# OSSI-1_COMMS_3.net
KiCad netlist of a schematic drawn in Altium Designer
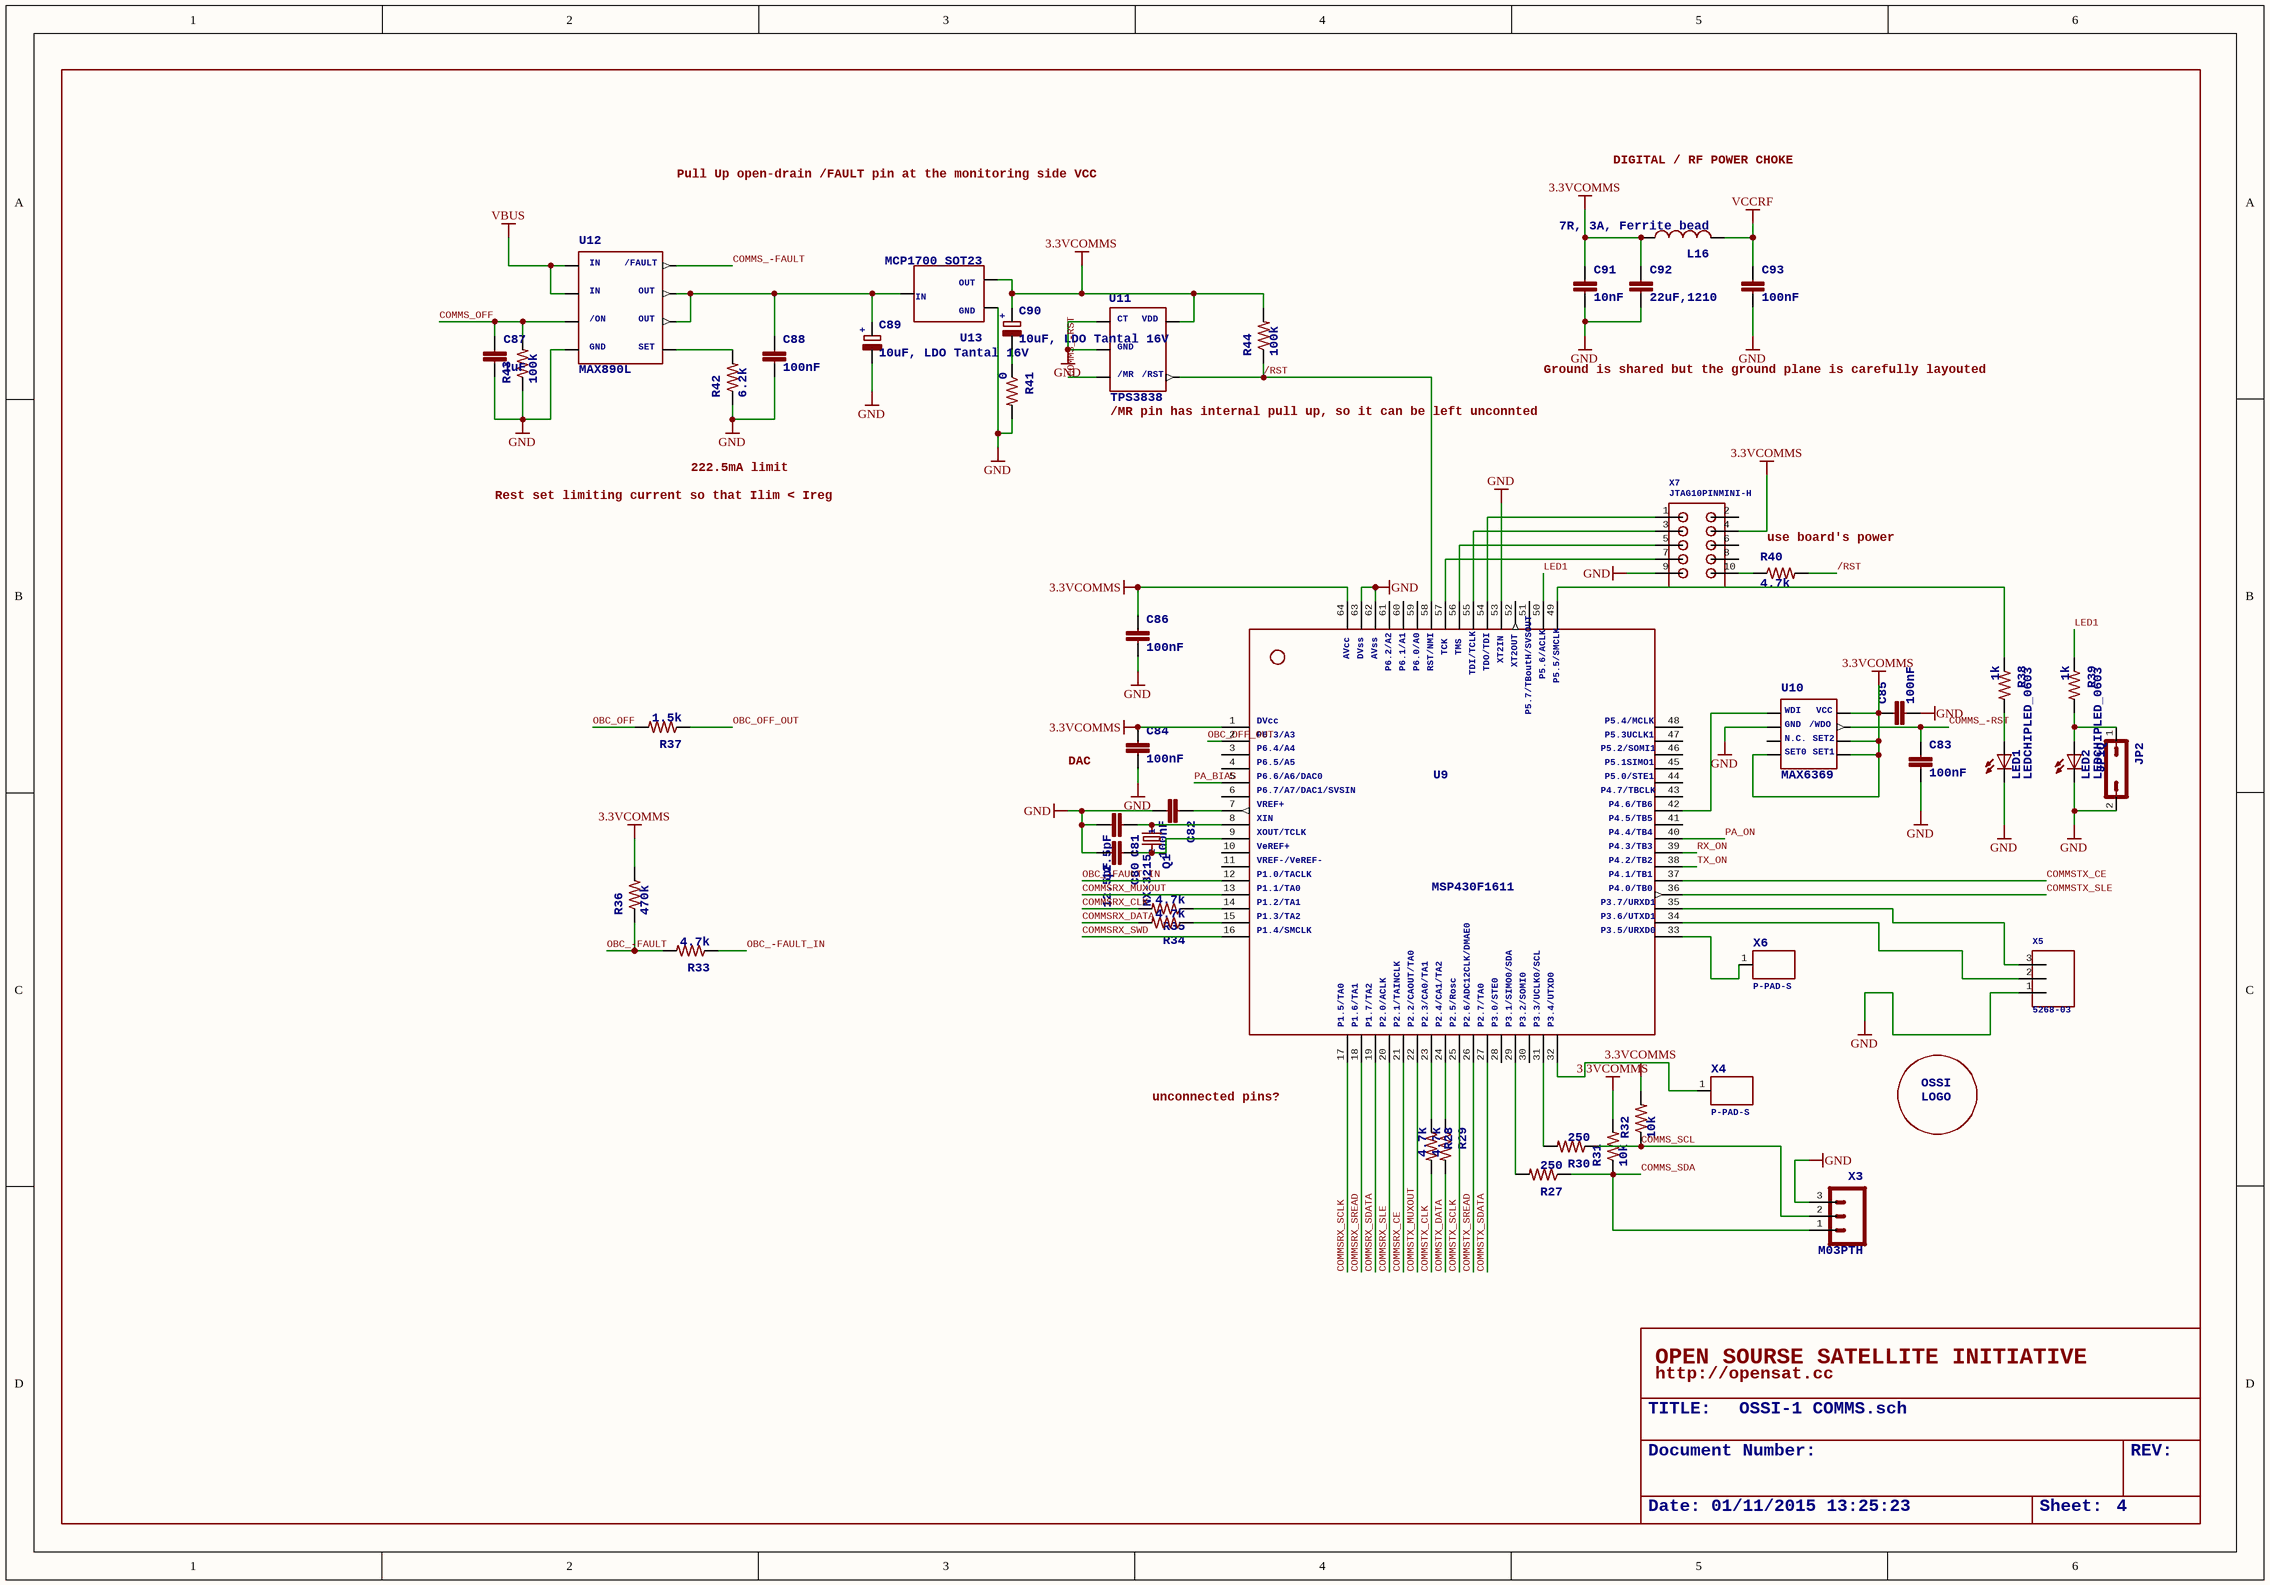
[diagram p0: OSSI-1 COMMS_3.SchDoc]

(export (version "E")
  (design (tool "Eeschema 10.0.6"))
  (components
    (comp (ref "C80")
      (value "12.5pF")
      (footprint "C0603(1608)")
      (fields (field (name ">NAME") "C80") (field (name ">VALUE") "12.5pF"))
      (libsource (lib "OSSI") (part "C0603(1608)"))
    )
    (comp (ref "C81")
      (value "12.5pF")
      (footprint "C0603(1608)")
      (fields (field (name ">NAME") "C81") (field (name ">VALUE") "12.5pF"))
      (libsource (lib "OSSI") (part "C0603(1608)"))
    )
    (comp (ref "C82")
      (value "100nF")
      (footprint "C0603(1608)")
      (fields (field (name ">NAME") "C82") (field (name ">VALUE") "100nF"))
      (libsource (lib "OSSI") (part "C0603(1608)"))
    )
    (comp (ref "C83")
      (value "100nF")
      (footprint "C0603(1608)")
      (fields (field (name ">NAME") "C83") (field (name ">VALUE") "100nF"))
      (libsource (lib "") (part "C0603(1608)_1"))
    )
    (comp (ref "C84")
      (value "100nF")
      (footprint "C0603(1608)")
      (fields (field (name ">NAME") "C84") (field (name ">VALUE") "100nF"))
      (libsource (lib "") (part "C0603(1608)_1"))
    )
    (comp (ref "C85")
      (value "100nF")
      (footprint "C0603(1608)")
      (fields (field (name ">NAME") "C85") (field (name ">VALUE") "100nF"))
      (libsource (lib "") (part "C0603(1608)_2"))
    )
    (comp (ref "C86")
      (value "100nF")
      (footprint "C0603(1608)")
      (fields (field (name ">NAME") "C86") (field (name ">VALUE") "100nF"))
      (libsource (lib "") (part "C0603(1608)_1"))
    )
    (comp (ref "C87")
      (value "1uF")
      (footprint "C0603(1608)")
      (fields (field (name ">NAME") "C87") (field (name ">VALUE") "1uF"))
      (libsource (lib "") (part "C0603(1608)_1"))
    )
    (comp (ref "C88")
      (value "100nF")
      (footprint "C0603(1608)")
      (fields (field (name ">NAME") "C88") (field (name ">VALUE") "100nF"))
      (libsource (lib "") (part "C0603(1608)_1"))
    )
    (comp (ref "C89")
      (value "10uF, LDO Tantal 16V")
      (footprint "C1206(3216)-A")
      (fields
        (field (name ">NAME") "C89")
        (field (name "+") "+")
        (field (name ">VALUE") "10uF, LDO Tantal 16V")
      )
      (libsource (lib "OSSI") (part "C-TANTAL-A"))
    )
    (comp (ref "C90")
      (value "10uF, LDO Tantal 16V")
      (footprint "C1206(3216)-A")
      (fields
        (field (name ">NAME") "C90")
        (field (name "+") "+")
        (field (name ">VALUE") "10uF, LDO Tantal 16V")
      )
      (libsource (lib "OSSI") (part "C-TANTAL-A"))
    )
    (comp (ref "C91")
      (value "10nF")
      (footprint "C0603(1608)")
      (fields (field (name ">NAME") "C91") (field (name ">VALUE") "10nF"))
      (libsource (lib "") (part "C0603(1608)_1"))
    )
    (comp (ref "C92")
      (value "22uF,1210")
      (footprint "C1210-GCM32")
      (fields (field (name ">NAME") "C92") (field (name ">VALUE") "22uF,1210"))
      (libsource (lib "OSSI") (part "C1210(3225)-GCM32"))
    )
    (comp (ref "C93")
      (value "100nF")
      (footprint "C0603(1608)")
      (fields (field (name ">NAME") "C93") (field (name ">VALUE") "100nF"))
      (libsource (lib "") (part "C0603(1608)_1"))
    )
    (comp (ref "JP2")
      (value "JP1Q")
      (footprint "JP1")
      (description "<b>JUMPER</b>")
      (fields (field (name ">NAME") "JP2") (field (name ">VALUE") "JP1Q"))
      (libsource (lib "OSSI") (part "JP1Q"))
    )
    (comp (ref "L16")
      (value "7R, 3A, Ferrite bead")
      (footprint "L0805(2012)")
      (fields (field (name ">NAME") "L16") (field (name ">VALUE") "7R, 3A, Ferrite bead"))
      (libsource (lib "OSSI") (part "L0805(2012)"))
    )
    (comp (ref "LED1")
      (value "LEDCHIPLED_0603")
      (footprint "CHIPLED_0603")
      (fields (field (name ">NAME") "LED1") (field (name ">VALUE") "LEDCHIPLED_0603"))
      (libsource (lib "led") (part "LEDCHIPLED_0603"))
    )
    (comp (ref "LED2")
      (value "LEDCHIPLED_0603")
      (footprint "CHIPLED_0603")
      (fields (field (name ">NAME") "LED2") (field (name ">VALUE") "LEDCHIPLED_0603"))
      (libsource (lib "led") (part "LEDCHIPLED_0603"))
    )
    (comp (ref "Q1")
      (value "NX-3215")
      (footprint "NX-3215")
      (fields
        (field (name ">NAME") "Q1")
        (field (name ">VALUE") "NX-3215")
        (field (name "1") "1")
        (field (name "2") "2")
      )
      (libsource (lib "OSSI") (part "NX-3215"))
    )
    (comp (ref "R27")
      (value "250")
      (footprint "R0603(1608)")
      (fields (field (name ">NAME") "R27") (field (name ">VALUE") "250"))
      (libsource (lib "OSSI") (part "R0603(1608)"))
    )
    (comp (ref "R28")
      (value "4.7k")
      (footprint "R0603(1608)")
      (fields (field (name ">NAME") "R28") (field (name ">VALUE") "4.7k"))
      (libsource (lib "OSSI") (part "R0603(1608)"))
    )
    (comp (ref "R29")
      (value "4.7k")
      (footprint "R0603(1608)")
      (fields (field (name ">NAME") "R29") (field (name ">VALUE") "4.7k"))
      (libsource (lib "OSSI") (part "R0603(1608)"))
    )
    (comp (ref "R30")
      (value "250")
      (footprint "R0603(1608)")
      (fields (field (name ">NAME") "R30") (field (name ">VALUE") "250"))
      (libsource (lib "OSSI") (part "R0603(1608)"))
    )
    (comp (ref "R31")
      (value "10k")
      (footprint "R0603(1608)")
      (fields (field (name ">NAME") "R31") (field (name ">VALUE") "10k"))
      (libsource (lib "OSSI") (part "R0603(1608)"))
    )
    (comp (ref "R32")
      (value "10k")
      (footprint "R0603(1608)")
      (fields (field (name ">NAME") "R32") (field (name ">VALUE") "10k"))
      (libsource (lib "OSSI") (part "R0603(1608)"))
    )
    (comp (ref "R33")
      (value "4.7k")
      (footprint "R0603(1608)")
      (fields (field (name ">NAME") "R33") (field (name ">VALUE") "4.7k"))
      (libsource (lib "OSSI") (part "R0603(1608)"))
    )
    (comp (ref "R34")
      (value "4.7k")
      (footprint "R0603(1608)")
      (fields (field (name ">NAME") "R34") (field (name ">VALUE") "4.7k"))
      (libsource (lib "OSSI") (part "R0603(1608)"))
    )
    (comp (ref "R35")
      (value "4.7k")
      (footprint "R0603(1608)")
      (fields (field (name ">NAME") "R35") (field (name ">VALUE") "4.7k"))
      (libsource (lib "OSSI") (part "R0603(1608)"))
    )
    (comp (ref "R36")
      (value "470k")
      (footprint "R0603(1608)")
      (fields (field (name ">NAME") "R36") (field (name ">VALUE") "470k"))
      (libsource (lib "OSSI") (part "R0603(1608)"))
    )
    (comp (ref "R37")
      (value "1.5k")
      (footprint "R0603(1608)")
      (fields (field (name ">NAME") "R37") (field (name ">VALUE") "1.5k"))
      (libsource (lib "OSSI") (part "R0603(1608)"))
    )
    (comp (ref "R38")
      (value "1k")
      (footprint "R0603(1608)")
      (fields (field (name ">NAME") "R38") (field (name ">VALUE") "1k"))
      (libsource (lib "OSSI") (part "R0603(1608)"))
    )
    (comp (ref "R39")
      (value "1k")
      (footprint "R0603(1608)")
      (fields (field (name ">NAME") "R39") (field (name ">VALUE") "1k"))
      (libsource (lib "OSSI") (part "R0603(1608)"))
    )
    (comp (ref "R40")
      (value "4.7k")
      (footprint "R0603(1608)")
      (fields (field (name ">NAME") "R40") (field (name ">VALUE") "4.7k"))
      (libsource (lib "OSSI") (part "R0603(1608)"))
    )
    (comp (ref "R41")
      (value "0")
      (footprint "R0603(1608)")
      (fields (field (name ">NAME") "R41") (field (name ">VALUE") "0"))
      (libsource (lib "OSSI") (part "R0603(1608)"))
    )
    (comp (ref "R42")
      (value "6.2k")
      (footprint "R0603(1608)")
      (fields (field (name ">NAME") "R42") (field (name ">VALUE") "6.2k"))
      (libsource (lib "OSSI") (part "R0603(1608)"))
    )
    (comp (ref "R43")
      (value "100k")
      (footprint "R0603(1608)")
      (fields (field (name ">NAME") "R43") (field (name ">VALUE") "100k"))
      (libsource (lib "OSSI") (part "R0603(1608)"))
    )
    (comp (ref "R44")
      (value "100k")
      (footprint "R0603(1608)")
      (fields (field (name ">NAME") "R44") (field (name ">VALUE") "100k"))
      (libsource (lib "OSSI") (part "R0603(1608)"))
    )
    (comp (ref "U$1")
      (value "OSSILOGORECT")
      (footprint "OSSILOGORECT1005")
      (fields (field (name "OSSI") "OSSI") (field (name "LOGO") "LOGO"))
      (libsource (lib "OSSI") (part "OSSILOGORECT"))
    )
    (comp (ref "U9")
      (value "MSP430F1611")
      (footprint "PM/PAG64")
      (description "<b>MSP430F1611</b>")
      (fields
        (field (name "AVCC") "AVcc")
        (field (name "DVSS") "DVss")
        (field (name "AVSS") "AVss")
        (field (name "P6.2/A2") "P6.2/A2")
        (field (name "P6.1/A1") "P6.1/A1")
        (field (name "P6.0/A0") "P6.0/A0")
        (field (name "RST/NMI") "RST/NMI")
        (field (name "TCK") "TCK")
        (field (name "TMS") "TMS")
        (field (name "TDI/TCLK") "TDI/TCLK")
        (field (name "TDO/TDI") "TDO/TDI")
        (field (name "XT2IN") "XT2IN")
        (field (name "XT2OUT") "XT2OUT")
        (field (name "P5.7/TBOUTH/SVSOUT") "P5.7/TBoutH/SVSOUT")
        (field (name "P5.6/ACLK") "P5.6/ACLK")
        (field (name "P5.5/SMCLK") "P5.5/SMCLK")
        (field (name "DVCC") "DVcc")
        (field (name "P6.3/A3") "P6.3/A3")
        (field (name "P6.4/A4") "P6.4/A4")
        (field (name "P6.5/A5") "P6.5/A5")
        (field (name "P6.6/A6/DAC0") "P6.6/A6/DAC0")
        (field (name "P6.7/A7/DAC1/SVSIN") "P6.7/A7/DAC1/SVSIN")
        (field (name "VREF+") "VREF+")
        (field (name "XIN") "XIN")
        (field (name "XOUT/TCLK") "XOUT/TCLK")
        (field (name "VEREF+") "VeREF+")
        (field (name "VREF-/VEREF-") "VREF-/VeREF-")
        (field (name "P1.0/TACLK") "P1.0/TACLK")
        (field (name "P1.1/TA0") "P1.1/TA0")
        (field (name "P1.2/TA1") "P1.2/TA1")
        (field (name "P1.3/TA2") "P1.3/TA2")
        (field (name "P1.4/SMCLK") "P1.4/SMCLK")
        (field (name "P1.5/TA0") "P1.5/TA0")
        (field (name "P1.6/TA1") "P1.6/TA1")
        (field (name "P1.7/TA2") "P1.7/TA2")
        (field (name "P2.0/ACLK") "P2.0/ACLK")
        (field (name "P2.1/TAINCLK") "P2.1/TAINCLK")
        (field (name "P2.2/CAOUT/TA0") "P2.2/CAOUT/TA0")
        (field (name "P2.3/CA0/TA1") "P2.3/CA0/TA1")
        (field (name "P2.4/CA1/TA2") "P2.4/CA1/TA2")
        (field (name "P2.5/ROSC") "P2.5/Rosc")
        (field (name "P2.6/ADC12CLK/DMAE0") "P2.6/ADC12CLK/DMAE0")
        (field (name "P2.7/TA0") "P2.7/TA0")
        (field (name "P3.0/STE0") "P3.0/STE0")
        (field (name "P3.1/SIMO0/SDA") "P3.1/SIMO0/SDA")
        (field (name "P3.2/SOMI0") "P3.2/SOMI0")
        (field (name "P3.3/UCLK0/SCL") "P3.3/UCLK0/SCL")
        (field (name "P3.4/UTXD0") "P3.4/UTXD0")
        (field (name "P5.4/MCLK") "P5.4/MCLK")
        (field (name "P5.3UCLK1") "P5.3UCLK1")
        (field (name "P5.2/SOMI1") "P5.2/SOMI1")
        (field (name "P5.1SIMO1") "P5.1SIMO1")
        (field (name "P5.0/STE1") "P5.0/STE1")
        (field (name "P4.7/TBCLK") "P4.7/TBCLK")
        (field (name "P4.6/TB6") "P4.6/TB6")
        (field (name "P4.5/TB5") "P4.5/TB5")
        (field (name "P4.4/TB4") "P4.4/TB4")
        (field (name "P4.3/TB3") "P4.3/TB3")
        (field (name "P4.2/TB2") "P4.2/TB2")
        (field (name "P4.1/TB1") "P4.1/TB1")
        (field (name "P4.0/TB0") "P4.0/TB0")
        (field (name "P3.7/URXD1") "P3.7/URXD1")
        (field (name "P3.6/UTXD1") "P3.6/UTXD1")
        (field (name "P3.5/URXD0") "P3.5/URXD0")
        (field (name ">VALUE") "MSP430F1611")
        (field (name ">NAME") "U9")
      )
      (libsource (lib "OSSI") (part "MSP430F1611"))
    )
    (comp (ref "U10")
      (value "MAX6369")
      (footprint "SOT23-8")
      (fields
        (field (name "WDI") "WDI")
        (field (name "GND") "GND")
        (field (name "N.C.") "N.C.")
        (field (name "SET0") "SET0")
        (field (name "SET1") "SET1")
        (field (name "SET2") "SET2")
        (field (name "/WDO") "/WDO")
        (field (name "VCC") "VCC")
        (field (name ">NAME") "U10")
        (field (name ">VALUE") "MAX6369")
      )
      (libsource (lib "OSSI") (part "MAX6369"))
    )
    (comp (ref "U11")
      (value "TPS3838")
      (footprint "SOT23-5DBV")
      (fields
        (field (name ">NAME") "U11")
        (field (name ">VALUE") "TPS3838")
        (field (name "CT") "CT")
        (field (name "/MR") "/MR")
        (field (name "GND") "GND")
        (field (name "VDD") "VDD")
        (field (name "/RST") "/RST")
      )
      (libsource (lib "OSSI") (part "TPS3838"))
    )
    (comp (ref "U12")
      (value "MAX890L")
      (footprint "SO8")
      (fields
        (field (name "IN") "IN")
        (field (name "IN_1") "IN")
        (field (name "/ON") "/ON")
        (field (name "GND") "GND")
        (field (name "SET") "SET")
        (field (name "OUT") "OUT")
        (field (name "OUT_1") "OUT")
        (field (name "/FAULT") "/FAULT")
        (field (name ">NAME") "U12")
        (field (name ">VALUE") "MAX890L")
      )
      (libsource (lib "OSSI") (part "MAX890L"))
    )
    (comp (ref "U13")
      (value "MCP1700_SOT23")
      (footprint "SOT23")
      (description "MCP1700 LDO from Microchips")
      (fields
        (field (name ">NAME") "U13")
        (field (name ">VALUE") "MCP1700_SOT23")
        (field (name "IN") "IN")
        (field (name "GND") "GND")
        (field (name "OUT") "OUT")
      )
      (libsource (lib "OSSI") (part "MCP1700_SOT23"))
    )
    (comp (ref "X3")
      (value "M03PTH")
      (footprint "1X03")
      (fields (field (name ">VALUE") "M03PTH") (field (name ">NAME") "X3"))
      (libsource (lib "OSSI") (part "M03PTH"))
    )
    (comp (ref "X4")
      (value "P-PAD-S")
      (footprint "P-PAD-S")
      (fields (field (name ">NAME") "X4") (field (name ">VALUE") "P-PAD-S"))
      (libsource (lib "OSSI") (part "P-PAD-S"))
    )
    (comp (ref "X5")
      (value "5268-03")
      (footprint "5268-03")
      (fields (field (name ">NAME") "X5") (field (name ">VALUE") "5268-03"))
      (libsource (lib "OSSI") (part "5268-03"))
    )
    (comp (ref "X6")
      (value "P-PAD-S")
      (footprint "P-PAD-S")
      (fields (field (name ">NAME") "X6") (field (name ">VALUE") "P-PAD-S"))
      (libsource (lib "OSSI") (part "P-PAD-S"))
    )
    (comp (ref "X7")
      (value "JTAG10PINMINI-H")
      (footprint "M50-3200545")
      (fields (field (name ">NAME") "X7") (field (name ">VALUE") "JTAG10PINMINI-H"))
      (libsource (lib "OSSI") (part "JTAG10PINMINI-H"))
    )
  )
  (nets
    (net (code "1") (name "/COMMSRX_CE") (class "Default")
      (node (ref "U9") (pin "21") (pinfunction "21_21") (pintype "passive"))
    )
    (net (code "2") (name "/COMMSRX_CLK") (class "Default")
      (node (ref "R35") (pin "2") (pinfunction "2_2") (pintype "passive"))
    )
    (net (code "3") (name "/COMMSRX_DATA") (class "Default")
      (node (ref "R34") (pin "2") (pinfunction "2_2") (pintype "passive"))
    )
    (net (code "4") (name "/COMMSRX_MUXOUT") (class "Default")
      (node (ref "U9") (pin "13") (pinfunction "13_13") (pintype "passive"))
    )
    (net (code "5") (name "/COMMSRX_SCLK") (class "Default")
      (node (ref "U9") (pin "17") (pinfunction "17_17") (pintype "passive"))
    )
    (net (code "6") (name "/COMMSRX_SDATA") (class "Default")
      (node (ref "U9") (pin "19") (pinfunction "19_19") (pintype "passive"))
    )
    (net (code "7") (name "/COMMSRX_SLE") (class "Default")
      (node (ref "U9") (pin "20") (pinfunction "20_20") (pintype "passive"))
    )
    (net (code "8") (name "/COMMSRX_SREAD") (class "Default")
      (node (ref "U9") (pin "18") (pinfunction "18_18") (pintype "passive"))
    )
    (net (code "9") (name "/COMMSRX_SWD") (class "Default")
      (node (ref "U9") (pin "16") (pinfunction "16_16") (pintype "passive"))
    )
    (net (code "10") (name "/COMMSTX_CE") (class "Default")
      (node (ref "U9") (pin "37") (pinfunction "37_37") (pintype "passive"))
    )
    (net (code "11") (name "/COMMSTX_CLK") (class "Default")
      (node (ref "R28") (pin "2") (pinfunction "2_2") (pintype "passive"))
    )
    (net (code "12") (name "/COMMSTX_DATA") (class "Default")
      (node (ref "R29") (pin "2") (pinfunction "2_2") (pintype "passive"))
    )
    (net (code "13") (name "/COMMSTX_MUXOUT") (class "Default")
      (node (ref "U9") (pin "22") (pinfunction "22_22") (pintype "passive"))
    )
    (net (code "14") (name "/COMMSTX_SCLK") (class "Default")
      (node (ref "U9") (pin "25") (pinfunction "25_25") (pintype "passive"))
    )
    (net (code "15") (name "/COMMSTX_SDATA") (class "Default")
      (node (ref "U9") (pin "27") (pinfunction "27_27") (pintype "passive"))
    )
    (net (code "16") (name "/COMMSTX_SLE") (class "Default")
      (node (ref "U9") (pin "36") (pinfunction "36_36") (pintype "output"))
    )
    (net (code "17") (name "/COMMSTX_SREAD") (class "Default")
      (node (ref "U9") (pin "26") (pinfunction "26_26") (pintype "passive"))
    )
    (net (code "18") (name "/COMMS_-FAULT") (class "Default")
      (node (ref "U12") (pin "8") (pinfunction "P$8_8") (pintype "output"))
    )
    (net (code "19") (name "/COMMS_-RST") (class "Default")
      (node (ref "C83") (pin "1") (pinfunction "1_1") (pintype "passive"))
      (node (ref "U10") (pin "7") (pinfunction "P$7_7") (pintype "output"))
      (node (ref "U11") (pin "3") (pinfunction "P$3_3") (pintype "passive"))
    )
    (net (code "20") (name "/COMMS_OFF") (class "Default")
      (node (ref "C87") (pin "1") (pinfunction "1_1") (pintype "passive"))
      (node (ref "R43") (pin "2") (pinfunction "2_2") (pintype "passive"))
      (node (ref "U12") (pin "3") (pinfunction "P$3_3") (pintype "passive"))
    )
    (net (code "21") (name "/COMMS_SCL") (class "Default")
      (node (ref "R30") (pin "1") (pinfunction "1_1") (pintype "passive"))
      (node (ref "R32") (pin "1") (pinfunction "1_1") (pintype "passive"))
      (node (ref "X3") (pin "2") (pinfunction "2_2") (pintype "passive"))
    )
    (net (code "22") (name "/COMMS_SDA") (class "Default")
      (node (ref "R27") (pin "1") (pinfunction "1_1") (pintype "passive"))
      (node (ref "R31") (pin "1") (pinfunction "1_1") (pintype "passive"))
      (node (ref "X3") (pin "1") (pinfunction "1_1") (pintype "passive"))
    )
    (net (code "23") (name "/LED1") (class "Default")
      (node (ref "R39") (pin "1") (pinfunction "1_1") (pintype "passive"))
      (node (ref "U9") (pin "50") (pinfunction "50_50") (pintype "passive"))
    )
    (net (code "24") (name "/OBC_-FAULT") (class "Default")
      (node (ref "R33") (pin "2") (pinfunction "2_2") (pintype "passive"))
      (node (ref "R36") (pin "1") (pinfunction "1_1") (pintype "passive"))
    )
    (net (code "25") (name "/OBC_-FAULT_IN") (class "Default")
      (node (ref "R33") (pin "1") (pinfunction "1_1") (pintype "passive"))
      (node (ref "U9") (pin "12") (pinfunction "12_12") (pintype "passive"))
    )
    (net (code "26") (name "/OBC_OFF") (class "Default")
      (node (ref "R37") (pin "2") (pinfunction "2_2") (pintype "passive"))
    )
    (net (code "27") (name "/OBC_OFF_OUT") (class "Default")
      (node (ref "R37") (pin "1") (pinfunction "1_1") (pintype "passive"))
      (node (ref "U9") (pin "2") (pinfunction "2_2") (pintype "passive"))
    )
    (net (code "28") (name "/PA_BIAS") (class "Default")
      (node (ref "U9") (pin "5") (pinfunction "5_5") (pintype "passive"))
    )
    (net (code "29") (name "/PA_ON") (class "Default")
      (node (ref "U9") (pin "40") (pinfunction "40_40") (pintype "passive"))
    )
    (net (code "30") (name "/RX_ON") (class "Default")
      (node (ref "U9") (pin "39") (pinfunction "39_39") (pintype "passive"))
    )
    (net (code "31") (name "/TX_ON") (class "Default")
      (node (ref "U9") (pin "38") (pinfunction "38_38") (pintype "passive"))
    )
    (net (code "32") (name "/{slash}RST") (class "Default")
      (node (ref "R40") (pin "2") (pinfunction "2_2") (pintype "passive"))
      (node (ref "R44") (pin "1") (pinfunction "1_1") (pintype "passive"))
      (node (ref "U11") (pin "4") (pinfunction "P$4_4") (pintype "output"))
      (node (ref "U9") (pin "58") (pinfunction "58_58") (pintype "passive"))
    )
    (net (code "33") (name "3.3VCOMMS") (class "Default")
      (node (ref "C84") (pin "1") (pinfunction "1_1") (pintype "passive"))
      (node (ref "C85") (pin "1") (pinfunction "1_1") (pintype "passive"))
      (node (ref "C86") (pin "1") (pinfunction "1_1") (pintype "passive"))
      (node (ref "C90") (pin "1") (pinfunction "+_1") (pintype "passive"))
      (node (ref "C91") (pin "1") (pinfunction "1_1") (pintype "passive"))
      (node (ref "C92") (pin "P$1") (pinfunction "1_P$1") (pintype "passive"))
      (node (ref "L16") (pin "1") (pinfunction "1_1") (pintype "passive"))
      (node (ref "R31") (pin "2") (pinfunction "2_2") (pintype "passive"))
      (node (ref "R32") (pin "2") (pinfunction "2_2") (pintype "passive"))
      (node (ref "R36") (pin "2") (pinfunction "2_2") (pintype "passive"))
      (node (ref "R44") (pin "2") (pinfunction "2_2") (pintype "passive"))
      (node (ref "U10") (pin "4") (pinfunction "P$4_4") (pintype "passive"))
      (node (ref "U10") (pin "5") (pinfunction "P$5_5") (pintype "passive"))
      (node (ref "U10") (pin "6") (pinfunction "P$6_6") (pintype "passive"))
      (node (ref "U10") (pin "8") (pinfunction "P$8_8") (pintype "power_in"))
      (node (ref "U11") (pin "5") (pinfunction "P$5_5") (pintype "power_in"))
      (node (ref "U13") (pin "2") (pinfunction "2_2") (pintype "power_in"))
      (node (ref "U9") (pin "1") (pinfunction "1_1") (pintype "power_in"))
      (node (ref "U9") (pin "64") (pinfunction "64_64") (pintype "power_in"))
      (node (ref "X7") (pin "4") (pinfunction "4_4") (pintype "passive"))
    )
    (net (code "34") (name "GND") (class "Default")
      (node (ref "C80") (pin "2") (pinfunction "2_2") (pintype "passive"))
      (node (ref "C81") (pin "2") (pinfunction "2_2") (pintype "passive"))
      (node (ref "C82") (pin "2") (pinfunction "2_2") (pintype "passive"))
      (node (ref "C83") (pin "2") (pinfunction "2_2") (pintype "passive"))
      (node (ref "C84") (pin "2") (pinfunction "2_2") (pintype "passive"))
      (node (ref "C85") (pin "2") (pinfunction "2_2") (pintype "passive"))
      (node (ref "C86") (pin "2") (pinfunction "2_2") (pintype "passive"))
      (node (ref "C87") (pin "2") (pinfunction "2_2") (pintype "passive"))
      (node (ref "C88") (pin "2") (pinfunction "2_2") (pintype "passive"))
      (node (ref "C89") (pin "2") (pinfunction "-_2") (pintype "passive"))
      (node (ref "C91") (pin "2") (pinfunction "2_2") (pintype "passive"))
      (node (ref "C92") (pin "P$2") (pinfunction "2_P$2") (pintype "passive"))
      (node (ref "C93") (pin "2") (pinfunction "2_2") (pintype "passive"))
      (node (ref "JP2") (pin "2") (pinfunction "2_2") (pintype "passive"))
      (node (ref "LED1") (pin "C") (pinfunction "C_C") (pintype "passive"))
      (node (ref "LED2") (pin "C") (pinfunction "C_C") (pintype "passive"))
      (node (ref "R41") (pin "2") (pinfunction "2_2") (pintype "passive"))
      (node (ref "R42") (pin "1") (pinfunction "1_1") (pintype "passive"))
      (node (ref "R43") (pin "1") (pinfunction "1_1") (pintype "passive"))
      (node (ref "U10") (pin "2") (pinfunction "P$2_2") (pintype "power_in"))
      (node (ref "U11") (pin "1") (pinfunction "P$1_1") (pintype "passive"))
      (node (ref "U11") (pin "2") (pinfunction "P$2_2") (pintype "power_in"))
      (node (ref "U12") (pin "4") (pinfunction "P$4_4") (pintype "power_in"))
      (node (ref "U13") (pin "1") (pinfunction "1_1") (pintype "power_in"))
      (node (ref "U9") (pin "53") (pinfunction "53_53") (pintype "passive"))
      (node (ref "U9") (pin "62") (pinfunction "62_62") (pintype "power_in"))
      (node (ref "U9") (pin "63") (pinfunction "63_63") (pintype "power_in"))
      (node (ref "X3") (pin "3") (pinfunction "3_3") (pintype "passive"))
      (node (ref "X5") (pin "1") (pinfunction "1_1") (pintype "passive"))
      (node (ref "X7") (pin "9") (pinfunction "9_9") (pintype "passive"))
    )
    (net (code "35") (name "Net-(C80-Pad1)") (class "Default")
      (node (ref "C80") (pin "1") (pinfunction "1_1") (pintype "passive"))
      (node (ref "Q1") (pin "2") (pinfunction "2_2") (pintype "passive"))
      (node (ref "U9") (pin "9") (pinfunction "9_9") (pintype "passive"))
    )
    (net (code "36") (name "Net-(C81-Pad1)") (class "Default")
      (node (ref "C81") (pin "1") (pinfunction "1_1") (pintype "passive"))
      (node (ref "Q1") (pin "1") (pinfunction "1_1") (pintype "passive"))
      (node (ref "U9") (pin "8") (pinfunction "8_8") (pintype "passive"))
    )
    (net (code "37") (name "Net-(C82-Pad1)") (class "Default")
      (node (ref "C82") (pin "1") (pinfunction "1_1") (pintype "passive"))
      (node (ref "U9") (pin "7") (pinfunction "7_7") (pintype "output"))
    )
    (net (code "38") (name "Net-(C89-+)") (class "Default")
      (node (ref "C88") (pin "1") (pinfunction "1_1") (pintype "passive"))
      (node (ref "C89") (pin "1") (pinfunction "+_1") (pintype "passive"))
      (node (ref "U12") (pin "6") (pinfunction "P$6_6") (pintype "output"))
      (node (ref "U12") (pin "7") (pinfunction "P$7_7") (pintype "output"))
      (node (ref "U13") (pin "3") (pinfunction "3_3") (pintype "power_in"))
    )
    (net (code "39") (name "Net-(C90--)") (class "Default")
      (node (ref "C90") (pin "2") (pinfunction "-_2") (pintype "passive"))
      (node (ref "R41") (pin "1") (pinfunction "1_1") (pintype "passive"))
    )
    (net (code "40") (name "Net-(JP2-Pad1)") (class "Default")
      (node (ref "JP2") (pin "1") (pinfunction "1_1") (pintype "passive"))
      (node (ref "LED2") (pin "A") (pinfunction "A_A") (pintype "passive"))
      (node (ref "R39") (pin "2") (pinfunction "2_2") (pintype "passive"))
    )
    (net (code "41") (name "Net-(LED1-PadA)") (class "Default")
      (node (ref "LED1") (pin "A") (pinfunction "A_A") (pintype "passive"))
      (node (ref "R38") (pin "2") (pinfunction "2_2") (pintype "passive"))
    )
    (net (code "42") (name "Net-(R27-Pad2)") (class "Default")
      (node (ref "R27") (pin "2") (pinfunction "2_2") (pintype "passive"))
      (node (ref "U9") (pin "29") (pinfunction "29_29") (pintype "passive"))
    )
    (net (code "43") (name "Net-(R28-Pad1)") (class "Default")
      (node (ref "R28") (pin "1") (pinfunction "1_1") (pintype "passive"))
      (node (ref "U9") (pin "23") (pinfunction "23_23") (pintype "passive"))
    )
    (net (code "44") (name "Net-(R29-Pad1)") (class "Default")
      (node (ref "R29") (pin "1") (pinfunction "1_1") (pintype "passive"))
      (node (ref "U9") (pin "24") (pinfunction "24_24") (pintype "passive"))
    )
    (net (code "45") (name "Net-(R30-Pad2)") (class "Default")
      (node (ref "R30") (pin "2") (pinfunction "2_2") (pintype "passive"))
      (node (ref "U9") (pin "31") (pinfunction "31_31") (pintype "passive"))
    )
    (net (code "46") (name "Net-(R34-Pad1)") (class "Default")
      (node (ref "R34") (pin "1") (pinfunction "1_1") (pintype "passive"))
      (node (ref "U9") (pin "15") (pinfunction "15_15") (pintype "passive"))
    )
    (net (code "47") (name "Net-(R35-Pad1)") (class "Default")
      (node (ref "R35") (pin "1") (pinfunction "1_1") (pintype "passive"))
      (node (ref "U9") (pin "14") (pinfunction "14_14") (pintype "passive"))
    )
    (net (code "48") (name "Net-(R38-Pad1)") (class "Default")
      (node (ref "R38") (pin "1") (pinfunction "1_1") (pintype "passive"))
      (node (ref "U9") (pin "49") (pinfunction "49_49") (pintype "passive"))
    )
    (net (code "49") (name "Net-(R40-Pad1)") (class "Default")
      (node (ref "R40") (pin "1") (pinfunction "1_1") (pintype "passive"))
      (node (ref "X7") (pin "10") (pinfunction "10_10") (pintype "passive"))
    )
    (net (code "50") (name "Net-(U9-Pad34)") (class "Default")
      (node (ref "U9") (pin "34") (pinfunction "34_34") (pintype "passive"))
      (node (ref "X5") (pin "2") (pinfunction "2_2") (pintype "passive"))
    )
    (net (code "51") (name "Net-(U9-Pad35)") (class "Default")
      (node (ref "U9") (pin "35") (pinfunction "35_35") (pintype "passive"))
      (node (ref "X5") (pin "3") (pinfunction "3_3") (pintype "passive"))
    )
    (net (code "52") (name "Net-(U9-Pad54)") (class "Default")
      (node (ref "U9") (pin "54") (pinfunction "54_54") (pintype "passive"))
      (node (ref "X7") (pin "1") (pinfunction "1_1") (pintype "passive"))
    )
    (net (code "53") (name "Net-(U9-Pad55)") (class "Default")
      (node (ref "U9") (pin "55") (pinfunction "55_55") (pintype "passive"))
      (node (ref "X7") (pin "3") (pinfunction "3_3") (pintype "passive"))
    )
    (net (code "54") (name "Net-(U9-Pad56)") (class "Default")
      (node (ref "U9") (pin "56") (pinfunction "56_56") (pintype "passive"))
      (node (ref "X7") (pin "5") (pinfunction "5_5") (pintype "passive"))
    )
    (net (code "55") (name "Net-(U9-Pad57)") (class "Default")
      (node (ref "U9") (pin "57") (pinfunction "57_57") (pintype "passive"))
      (node (ref "X7") (pin "7") (pinfunction "7_7") (pintype "passive"))
    )
    (net (code "56") (name "Net-(U10-P$1)") (class "Default")
      (node (ref "U10") (pin "1") (pinfunction "P$1_1") (pintype "passive"))
      (node (ref "U9") (pin "42") (pinfunction "42_42") (pintype "passive"))
    )
    (net (code "57") (name "Net-(U12-P$5)") (class "Default")
      (node (ref "R42") (pin "2") (pinfunction "2_2") (pintype "passive"))
      (node (ref "U12") (pin "5") (pinfunction "P$5_5") (pintype "passive"))
    )
    (net (code "58") (name "Net-(X4-P$1)") (class "Default")
      (node (ref "U9") (pin "32") (pinfunction "32_32") (pintype "passive"))
      (node (ref "X4") (pin "1") (pinfunction "P$1_1") (pintype "passive"))
    )
    (net (code "59") (name "Net-(X6-P$1)") (class "Default")
      (node (ref "U9") (pin "33") (pinfunction "33_33") (pintype "passive"))
      (node (ref "X6") (pin "1") (pinfunction "P$1_1") (pintype "passive"))
    )
    (net (code "60") (name "VBUS") (class "Default")
      (node (ref "U12") (pin "1") (pinfunction "P$1_1") (pintype "passive"))
      (node (ref "U12") (pin "2") (pinfunction "P$2_2") (pintype "passive"))
    )
    (net (code "61") (name "VCCRF") (class "Default")
      (node (ref "C93") (pin "1") (pinfunction "1_1") (pintype "passive"))
      (node (ref "L16") (pin "2") (pinfunction "2_2") (pintype "passive"))
    )
    (net (code "62") (name "unconnected-(U9-Pad3)") (class "Default")
      (node (ref "U9") (pin "3") (pinfunction "3_3") (pintype "passive"))
    )
    (net (code "63") (name "unconnected-(U9-Pad4)") (class "Default")
      (node (ref "U9") (pin "4") (pinfunction "4_4") (pintype "passive"))
    )
    (net (code "64") (name "unconnected-(U9-Pad6)") (class "Default")
      (node (ref "U9") (pin "6") (pinfunction "6_6") (pintype "passive"))
    )
    (net (code "65") (name "unconnected-(U9-Pad10)") (class "Default")
      (node (ref "U9") (pin "10") (pinfunction "10_10") (pintype "passive"))
    )
    (net (code "66") (name "unconnected-(U9-Pad11)") (class "Default")
      (node (ref "U9") (pin "11") (pinfunction "11_11") (pintype "passive"))
    )
    (net (code "67") (name "unconnected-(U9-Pad28)") (class "Default")
      (node (ref "U9") (pin "28") (pinfunction "28_28") (pintype "passive"))
    )
    (net (code "68") (name "unconnected-(U9-Pad30)") (class "Default")
      (node (ref "U9") (pin "30") (pinfunction "30_30") (pintype "passive"))
    )
    (net (code "69") (name "unconnected-(U9-Pad41)") (class "Default")
      (node (ref "U9") (pin "41") (pinfunction "41_41") (pintype "passive"))
    )
    (net (code "70") (name "unconnected-(U9-Pad43)") (class "Default")
      (node (ref "U9") (pin "43") (pinfunction "43_43") (pintype "passive"))
    )
    (net (code "71") (name "unconnected-(U9-Pad44)") (class "Default")
      (node (ref "U9") (pin "44") (pinfunction "44_44") (pintype "passive"))
    )
    (net (code "72") (name "unconnected-(U9-Pad45)") (class "Default")
      (node (ref "U9") (pin "45") (pinfunction "45_45") (pintype "passive"))
    )
    (net (code "73") (name "unconnected-(U9-Pad46)") (class "Default")
      (node (ref "U9") (pin "46") (pinfunction "46_46") (pintype "passive"))
    )
    (net (code "74") (name "unconnected-(U9-Pad47)") (class "Default")
      (node (ref "U9") (pin "47") (pinfunction "47_47") (pintype "passive"))
    )
    (net (code "75") (name "unconnected-(U9-Pad48)") (class "Default")
      (node (ref "U9") (pin "48") (pinfunction "48_48") (pintype "passive"))
    )
    (net (code "76") (name "unconnected-(U9-Pad51)") (class "Default")
      (node (ref "U9") (pin "51") (pinfunction "51_51") (pintype "passive"))
    )
    (net (code "77") (name "unconnected-(U9-Pad52)") (class "Default")
      (node (ref "U9") (pin "52") (pinfunction "52_52") (pintype "output"))
    )
    (net (code "78") (name "unconnected-(U9-Pad59)") (class "Default")
      (node (ref "U9") (pin "59") (pinfunction "59_59") (pintype "passive"))
    )
    (net (code "79") (name "unconnected-(U9-Pad60)") (class "Default")
      (node (ref "U9") (pin "60") (pinfunction "60_60") (pintype "passive"))
    )
    (net (code "80") (name "unconnected-(U9-Pad61)") (class "Default")
      (node (ref "U9") (pin "61") (pinfunction "61_61") (pintype "passive"))
    )
    (net (code "81") (name "unconnected-(U10-P$3-Pad3)") (class "Default")
      (node (ref "U10") (pin "3") (pinfunction "P$3_3") (pintype "passive"))
    )
    (net (code "82") (name "unconnected-(X7-Pad2)") (class "Default")
      (node (ref "X7") (pin "2") (pinfunction "2_2") (pintype "passive"))
    )
    (net (code "83") (name "unconnected-(X7-Pad6)") (class "Default")
      (node (ref "X7") (pin "6") (pinfunction "6_6") (pintype "passive"))
    )
    (net (code "84") (name "unconnected-(X7-Pad8)") (class "Default")
      (node (ref "X7") (pin "8") (pinfunction "8_8") (pintype "passive"))
    )
  )
)
